# Motor_Control.net
KiCad netlist of a schematic drawn in Altium Designer
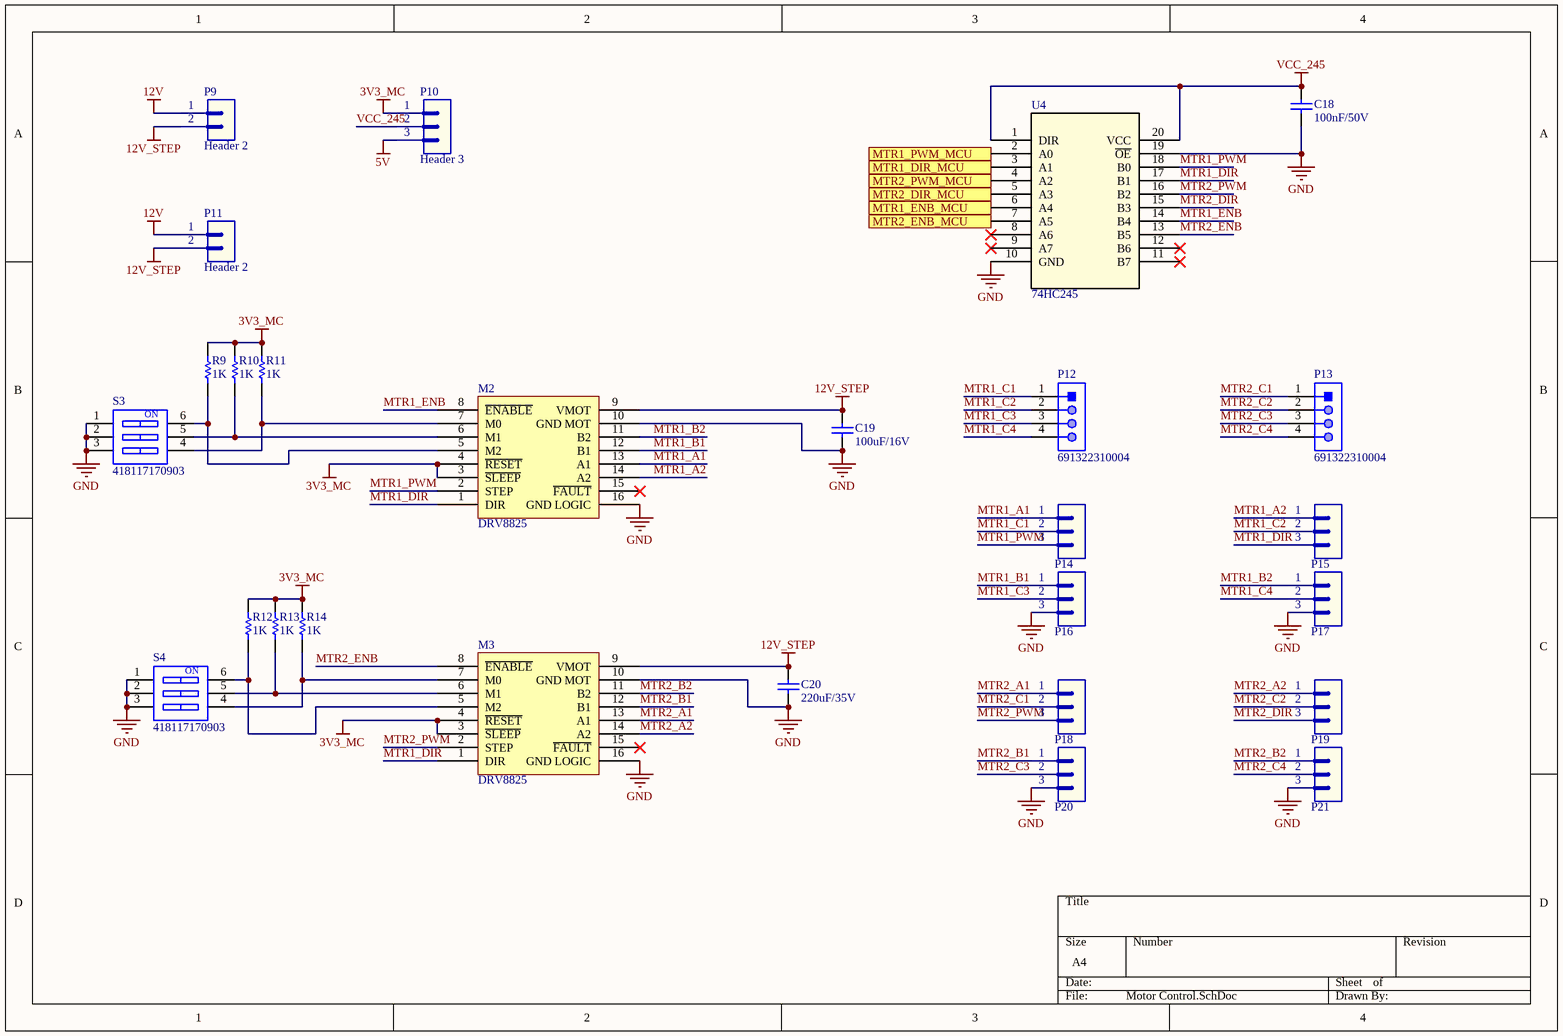
[diagram p0: Motor Control.SchDoc]

(export (version "E")
  (design (tool "Eeschema 10.0.6"))
  (components
    (comp (ref "C18")
      (value "100nF/50V")
      (footprint "CAP-SM-0805")
      (description "CAP CER 10UF 50V X5R 0805")
      (fields
        (field (name "MANUFACTURER") "Yageo")
        (field (name "MANUFACTURER PART NUMBER") "CC0805KKX5R9BB106")
      )
      (libsource (lib "Capacitor") (part "Cap-10uF-50V-0805"))
    )
    (comp (ref "C19")
      (value "100uF/16V")
      (footprint "CAP-SM-0805")
      (description "CAP CER 1000PF 100V X7R 0805")
      (fields
        (field (name "MANUFACTURER") "Johanson Dielectrics Inc.")
        (field (name "MANUFACTURER PART NUMBER") "101X15W102MV4E")
      )
      (libsource (lib "Capacitor") (part "Cap-1nF-50V-0805"))
    )
    (comp (ref "C20")
      (value "220uF/35V")
      (footprint "CAP-SM-0805")
      (description "CAP CER 1000PF 100V X7R 0805")
      (fields
        (field (name "MANUFACTURER") "Johanson Dielectrics Inc.")
        (field (name "MANUFACTURER PART NUMBER") "101X15W102MV4E")
      )
      (libsource (lib "Capacitor") (part "Cap-1nF-50V-0805"))
    )
    (comp (ref "M2") (value "DRV8825") (footprint "DRV8825") (libsource (lib "Schlib1") (part "DRV8825")))
    (comp (ref "M3") (value "DRV8825") (footprint "DRV8825") (libsource (lib "Schlib1") (part "DRV8825")))
    (comp (ref "P9")
      (value "Header 2")
      (footprint "JP2")
      (description "Header, 2-Pin")
      (fields (field (name "PUBLISHER") "Altium Limited"))
      (libsource (lib "PIF_C16_lib") (part "Header 2"))
    )
    (comp (ref "P10")
      (value "Header 3")
      (footprint "JP3")
      (description "Header, 3-Pin")
      (fields (field (name "PUBLISHER") "Altium Limited"))
      (libsource (lib "PIF_C16_lib") (part "Header 3"))
    )
    (comp (ref "P11")
      (value "Header 2")
      (footprint "JP2")
      (description "Header, 2-Pin")
      (fields (field (name "PUBLISHER") "Altium Limited"))
      (libsource (lib "PIF_C16_lib") (part "Header 2"))
    )
    (comp (ref "P12")
      (value "691322310004")
      (footprint "691322310004")
      (description "WR-TBL Serie 322 Horizontal PCB Header, Pluggable, pitch 3.81mm, 4p")
      (fields (field (name "PUBLISHER") "Wurth Elektronik"))
      (libsource (lib "691101710002_Altium_WR-TBL_rev19a") (part "691322310004"))
    )
    (comp (ref "P13")
      (value "691322310004")
      (footprint "691322310004")
      (description "WR-TBL Serie 322 Horizontal PCB Header, Pluggable, pitch 3.81mm, 4p")
      (fields (field (name "PUBLISHER") "Wurth Elektronik"))
      (libsource (lib "691101710002_Altium_WR-TBL_rev19a") (part "691322310004"))
    )
    (comp (ref "P14")
      (value "Header 3")
      (footprint "JP3")
      (description "Header, 3-Pin")
      (fields (field (name "PUBLISHER") "Altium Limited"))
      (libsource (lib "Header-connector") (part "Header 3"))
    )
    (comp (ref "P15")
      (value "Header 3")
      (footprint "JP3")
      (description "Header, 3-Pin")
      (fields (field (name "PUBLISHER") "Altium Limited"))
      (libsource (lib "Header-connector") (part "Header 3"))
    )
    (comp (ref "P16")
      (value "Header 3")
      (footprint "JP3")
      (description "Header, 3-Pin")
      (fields (field (name "PUBLISHER") "Altium Limited"))
      (libsource (lib "Header-connector") (part "Header 3"))
    )
    (comp (ref "P17")
      (value "Header 3")
      (footprint "JP3")
      (description "Header, 3-Pin")
      (fields (field (name "PUBLISHER") "Altium Limited"))
      (libsource (lib "Header-connector") (part "Header 3"))
    )
    (comp (ref "P18")
      (value "Header 3")
      (footprint "JP3")
      (description "Header, 3-Pin")
      (fields (field (name "PUBLISHER") "Altium Limited"))
      (libsource (lib "Header-connector") (part "Header 3"))
    )
    (comp (ref "P19")
      (value "Header 3")
      (footprint "JP3")
      (description "Header, 3-Pin")
      (fields (field (name "PUBLISHER") "Altium Limited"))
      (libsource (lib "Header-connector") (part "Header 3"))
    )
    (comp (ref "P20")
      (value "Header 3")
      (footprint "JP3")
      (description "Header, 3-Pin")
      (fields (field (name "PUBLISHER") "Altium Limited"))
      (libsource (lib "Header-connector") (part "Header 3"))
    )
    (comp (ref "P21")
      (value "Header 3")
      (footprint "JP3")
      (description "Header, 3-Pin")
      (fields (field (name "PUBLISHER") "Altium Limited"))
      (libsource (lib "Header-connector") (part "Header 3"))
    )
    (comp (ref "R9")
      (value "1K")
      (footprint "Resistor:RES-SM-0805")
      (description "RES 1K OHM 1% 1/4W 0805")
      (fields
        (field (name "MANUFACTURER") "Stackpole Electronics Inc")
        (field (name "MANUFACTURER PART NUMBER") "RNCP0805FTD1K00")
      )
      (libsource (lib "Resistor") (part "Res-1K-0805"))
    )
    (comp (ref "R10")
      (value "1K")
      (footprint "Resistor:RES-SM-0805")
      (description "RES 1K OHM 1% 1/4W 0805")
      (fields
        (field (name "MANUFACTURER") "Stackpole Electronics Inc")
        (field (name "MANUFACTURER PART NUMBER") "RNCP0805FTD1K00")
      )
      (libsource (lib "Resistor") (part "Res-1K-0805"))
    )
    (comp (ref "R11")
      (value "1K")
      (footprint "Resistor:RES-SM-0805")
      (description "RES 1K OHM 1% 1/4W 0805")
      (fields
        (field (name "MANUFACTURER") "Stackpole Electronics Inc")
        (field (name "MANUFACTURER PART NUMBER") "RNCP0805FTD1K00")
      )
      (libsource (lib "Resistor") (part "Res-1K-0805"))
    )
    (comp (ref "R12")
      (value "1K")
      (footprint "Resistor:RES-SM-0805")
      (description "RES 1K OHM 1% 1/4W 0805")
      (fields
        (field (name "MANUFACTURER") "Stackpole Electronics Inc")
        (field (name "MANUFACTURER PART NUMBER") "RNCP0805FTD1K00")
      )
      (libsource (lib "Resistor") (part "Res-1K-0805"))
    )
    (comp (ref "R13")
      (value "1K")
      (footprint "Resistor:RES-SM-0805")
      (description "RES 1K OHM 1% 1/4W 0805")
      (fields
        (field (name "MANUFACTURER") "Stackpole Electronics Inc")
        (field (name "MANUFACTURER PART NUMBER") "RNCP0805FTD1K00")
      )
      (libsource (lib "Resistor") (part "Res-1K-0805"))
    )
    (comp (ref "R14")
      (value "1K")
      (footprint "Resistor:RES-SM-0805")
      (description "RES 1K OHM 1% 1/4W 0805")
      (fields
        (field (name "MANUFACTURER") "Stackpole Electronics Inc")
        (field (name "MANUFACTURER PART NUMBER") "RNCP0805FTD1K00")
      )
      (libsource (lib "Resistor") (part "Res-1K-0805"))
    )
    (comp (ref "S3")
      (value "418117170903")
      (footprint "418117170903")
      (description "WS-DITV Compact THT Dip Switch, Flat Actuator, pitch 2.54mm, 3p")
      (fields (field (name "PUBLISHER") "Wurth Elektronik"))
      (libsource (lib "418117170903_Altium_WS-DITV_rev19a") (part "418117170903"))
    )
    (comp (ref "S4")
      (value "418117170903")
      (footprint "418117170903")
      (description "WS-DITV Compact THT Dip Switch, Flat Actuator, pitch 2.54mm, 3p")
      (fields (field (name "PUBLISHER") "Wurth Elektronik"))
      (libsource (lib "418117170903_Altium_WS-DITV_rev19a") (part "418117170903"))
    )
    (comp (ref "U4")
      (value "74HC245")
      (footprint "74HC245,625")
      (description "No Description Available")
      (fields (field (name "COPYRIGHT") "Copyright (C) 2018 Accelerated Designs. All rights reserved"))
      (libsource (lib "Integrated_Library") (part "74HC245"))
    )
  )
  (nets
    (net (code "1") (name "/MTR1_A1") (class "Default")
      (node (ref "M2") (pin "13") (pinfunction "A1_13") (pintype "passive"))
      (node (ref "P14") (pin "1") (pinfunction "1_1") (pintype "passive"))
    )
    (net (code "2") (name "/MTR1_A2") (class "Default")
      (node (ref "M2") (pin "14") (pinfunction "A2_14") (pintype "passive"))
      (node (ref "P15") (pin "1") (pinfunction "1_1") (pintype "passive"))
    )
    (net (code "3") (name "/MTR1_B1") (class "Default")
      (node (ref "M2") (pin "12") (pinfunction "B1_12") (pintype "passive"))
      (node (ref "P16") (pin "1") (pinfunction "1_1") (pintype "passive"))
    )
    (net (code "4") (name "/MTR1_B2") (class "Default")
      (node (ref "M2") (pin "11") (pinfunction "B2_11") (pintype "passive"))
      (node (ref "P17") (pin "1") (pinfunction "1_1") (pintype "passive"))
    )
    (net (code "5") (name "/MTR1_C1") (class "Default")
      (node (ref "P12") (pin "1") (pinfunction "1_1") (pintype "passive"))
      (node (ref "P14") (pin "2") (pinfunction "2_2") (pintype "passive"))
    )
    (net (code "6") (name "/MTR1_C2") (class "Default")
      (node (ref "P12") (pin "2") (pinfunction "2_2") (pintype "passive"))
      (node (ref "P15") (pin "2") (pinfunction "2_2") (pintype "passive"))
    )
    (net (code "7") (name "/MTR1_C3") (class "Default")
      (node (ref "P12") (pin "3") (pinfunction "3_3") (pintype "passive"))
      (node (ref "P16") (pin "2") (pinfunction "2_2") (pintype "passive"))
    )
    (net (code "8") (name "/MTR1_C4") (class "Default")
      (node (ref "P12") (pin "4") (pinfunction "4_4") (pintype "passive"))
      (node (ref "P17") (pin "2") (pinfunction "2_2") (pintype "passive"))
    )
    (net (code "9") (name "/MTR1_DIR") (class "Default")
      (node (ref "M2") (pin "1") (pinfunction "DIR_1") (pintype "passive"))
      (node (ref "M3") (pin "1") (pinfunction "DIR_1") (pintype "passive"))
      (node (ref "P15") (pin "3") (pinfunction "3_3") (pintype "passive"))
      (node (ref "U4") (pin "17") (pinfunction "B1_17") (pintype "passive"))
    )
    (net (code "10") (name "/MTR1_DIR_MCU") (class "Default")
      (node (ref "U4") (pin "3") (pinfunction "A1_3") (pintype "passive"))
    )
    (net (code "11") (name "/MTR1_ENB") (class "Default")
      (node (ref "M2") (pin "8") (pinfunction "~{ENABLE}_8") (pintype "passive"))
      (node (ref "U4") (pin "14") (pinfunction "B4_14") (pintype "passive"))
    )
    (net (code "12") (name "/MTR1_ENB_MCU") (class "Default")
      (node (ref "U4") (pin "6") (pinfunction "A4_6") (pintype "passive"))
    )
    (net (code "13") (name "/MTR1_PWM") (class "Default")
      (node (ref "M2") (pin "2") (pinfunction "STEP_2") (pintype "passive"))
      (node (ref "P14") (pin "3") (pinfunction "3_3") (pintype "passive"))
      (node (ref "U4") (pin "18") (pinfunction "B0_18") (pintype "passive"))
    )
    (net (code "14") (name "/MTR1_PWM_MCU") (class "Default")
      (node (ref "U4") (pin "2") (pinfunction "A0_2") (pintype "passive"))
    )
    (net (code "15") (name "/MTR2_A1") (class "Default")
      (node (ref "M3") (pin "13") (pinfunction "A1_13") (pintype "passive"))
      (node (ref "P18") (pin "1") (pinfunction "1_1") (pintype "passive"))
    )
    (net (code "16") (name "/MTR2_A2") (class "Default")
      (node (ref "M3") (pin "14") (pinfunction "A2_14") (pintype "passive"))
      (node (ref "P19") (pin "1") (pinfunction "1_1") (pintype "passive"))
    )
    (net (code "17") (name "/MTR2_B1") (class "Default")
      (node (ref "M3") (pin "12") (pinfunction "B1_12") (pintype "passive"))
      (node (ref "P20") (pin "1") (pinfunction "1_1") (pintype "passive"))
    )
    (net (code "18") (name "/MTR2_B2") (class "Default")
      (node (ref "M3") (pin "11") (pinfunction "B2_11") (pintype "passive"))
      (node (ref "P21") (pin "1") (pinfunction "1_1") (pintype "passive"))
    )
    (net (code "19") (name "/MTR2_C1") (class "Default")
      (node (ref "P13") (pin "1") (pinfunction "1_1") (pintype "passive"))
      (node (ref "P18") (pin "2") (pinfunction "2_2") (pintype "passive"))
    )
    (net (code "20") (name "/MTR2_C2") (class "Default")
      (node (ref "P13") (pin "2") (pinfunction "2_2") (pintype "passive"))
      (node (ref "P19") (pin "2") (pinfunction "2_2") (pintype "passive"))
    )
    (net (code "21") (name "/MTR2_C3") (class "Default")
      (node (ref "P13") (pin "3") (pinfunction "3_3") (pintype "passive"))
      (node (ref "P20") (pin "2") (pinfunction "2_2") (pintype "passive"))
    )
    (net (code "22") (name "/MTR2_C4") (class "Default")
      (node (ref "P13") (pin "4") (pinfunction "4_4") (pintype "passive"))
      (node (ref "P21") (pin "2") (pinfunction "2_2") (pintype "passive"))
    )
    (net (code "23") (name "/MTR2_DIR") (class "Default")
      (node (ref "P19") (pin "3") (pinfunction "3_3") (pintype "passive"))
      (node (ref "U4") (pin "15") (pinfunction "B3_15") (pintype "passive"))
    )
    (net (code "24") (name "/MTR2_DIR_MCU") (class "Default")
      (node (ref "U4") (pin "5") (pinfunction "A3_5") (pintype "passive"))
    )
    (net (code "25") (name "/MTR2_ENB") (class "Default")
      (node (ref "M3") (pin "8") (pinfunction "~{ENABLE}_8") (pintype "passive"))
      (node (ref "U4") (pin "13") (pinfunction "B5_13") (pintype "passive"))
    )
    (net (code "26") (name "/MTR2_ENB_MCU") (class "Default")
      (node (ref "U4") (pin "7") (pinfunction "A5_7") (pintype "passive"))
    )
    (net (code "27") (name "/MTR2_PWM") (class "Default")
      (node (ref "M3") (pin "2") (pinfunction "STEP_2") (pintype "passive"))
      (node (ref "P18") (pin "3") (pinfunction "3_3") (pintype "passive"))
      (node (ref "U4") (pin "16") (pinfunction "B2_16") (pintype "passive"))
    )
    (net (code "28") (name "/MTR2_PWM_MCU") (class "Default")
      (node (ref "U4") (pin "4") (pinfunction "A2_4") (pintype "passive"))
    )
    (net (code "29") (name "3V3_MC") (class "Default")
      (node (ref "M2") (pin "3") (pinfunction "~{SLEEP}_3") (pintype "passive"))
      (node (ref "M2") (pin "4") (pinfunction "~{RESET}_4") (pintype "passive"))
      (node (ref "M3") (pin "3") (pinfunction "~{SLEEP}_3") (pintype "passive"))
      (node (ref "M3") (pin "4") (pinfunction "~{RESET}_4") (pintype "passive"))
      (node (ref "P10") (pin "1") (pinfunction "1_1") (pintype "passive"))
      (node (ref "R10") (pin "2") (pinfunction "2_2") (pintype "passive"))
      (node (ref "R11") (pin "2") (pinfunction "2_2") (pintype "passive"))
      (node (ref "R12") (pin "2") (pinfunction "2_2") (pintype "passive"))
      (node (ref "R13") (pin "2") (pinfunction "2_2") (pintype "passive"))
      (node (ref "R14") (pin "2") (pinfunction "2_2") (pintype "passive"))
      (node (ref "R9") (pin "2") (pinfunction "2_2") (pintype "passive"))
    )
    (net (code "30") (name "5V") (class "Default")
      (node (ref "P10") (pin "3") (pinfunction "3_3") (pintype "passive"))
    )
    (net (code "31") (name "12V") (class "Default")
      (node (ref "P11") (pin "1") (pinfunction "1_1") (pintype "passive"))
      (node (ref "P9") (pin "1") (pinfunction "1_1") (pintype "passive"))
    )
    (net (code "32") (name "12V_STEP") (class "Default")
      (node (ref "C19") (pin "2") (pinfunction "2_2") (pintype "passive"))
      (node (ref "C20") (pin "2") (pinfunction "2_2") (pintype "passive"))
      (node (ref "M2") (pin "9") (pinfunction "VMOT_9") (pintype "passive"))
      (node (ref "M3") (pin "9") (pinfunction "VMOT_9") (pintype "passive"))
      (node (ref "P11") (pin "2") (pinfunction "2_2") (pintype "passive"))
      (node (ref "P9") (pin "2") (pinfunction "2_2") (pintype "passive"))
    )
    (net (code "33") (name "GND") (class "Default")
      (node (ref "C18") (pin "1") (pinfunction "1_1") (pintype "passive"))
      (node (ref "C19") (pin "1") (pinfunction "1_1") (pintype "passive"))
      (node (ref "C20") (pin "1") (pinfunction "1_1") (pintype "passive"))
      (node (ref "M2") (pin "10") (pinfunction "GND_MOT_10") (pintype "passive"))
      (node (ref "M2") (pin "16") (pinfunction "GND_LOGIC_16") (pintype "passive"))
      (node (ref "M3") (pin "10") (pinfunction "GND_MOT_10") (pintype "passive"))
      (node (ref "M3") (pin "16") (pinfunction "GND_LOGIC_16") (pintype "passive"))
      (node (ref "P16") (pin "3") (pinfunction "3_3") (pintype "passive"))
      (node (ref "P17") (pin "3") (pinfunction "3_3") (pintype "passive"))
      (node (ref "P20") (pin "3") (pinfunction "3_3") (pintype "passive"))
      (node (ref "P21") (pin "3") (pinfunction "3_3") (pintype "passive"))
      (node (ref "S3") (pin "1") (pinfunction "1_1") (pintype "passive"))
      (node (ref "S3") (pin "2") (pinfunction "2_2") (pintype "passive"))
      (node (ref "S3") (pin "3") (pinfunction "3_3") (pintype "passive"))
      (node (ref "S4") (pin "1") (pinfunction "1_1") (pintype "passive"))
      (node (ref "S4") (pin "2") (pinfunction "2_2") (pintype "passive"))
      (node (ref "S4") (pin "3") (pinfunction "3_3") (pintype "passive"))
      (node (ref "U4") (pin "10") (pinfunction "GND_10") (pintype "passive"))
      (node (ref "U4") (pin "19") (pinfunction "~{OE}_19") (pintype "passive"))
    )
    (net (code "34") (name "Net-(M2-M0)") (class "Default")
      (node (ref "M2") (pin "7") (pinfunction "M0_7") (pintype "passive"))
      (node (ref "R11") (pin "1") (pinfunction "1_1") (pintype "passive"))
      (node (ref "S3") (pin "4") (pinfunction "4_4") (pintype "passive"))
    )
    (net (code "35") (name "Net-(M2-M1)") (class "Default")
      (node (ref "M2") (pin "6") (pinfunction "M1_6") (pintype "passive"))
      (node (ref "R10") (pin "1") (pinfunction "1_1") (pintype "passive"))
      (node (ref "S3") (pin "5") (pinfunction "5_5") (pintype "passive"))
    )
    (net (code "36") (name "Net-(M2-M2)") (class "Default")
      (node (ref "M2") (pin "5") (pinfunction "M2_5") (pintype "passive"))
      (node (ref "R9") (pin "1") (pinfunction "1_1") (pintype "passive"))
      (node (ref "S3") (pin "6") (pinfunction "6_6") (pintype "passive"))
    )
    (net (code "37") (name "Net-(M3-M0)") (class "Default")
      (node (ref "M3") (pin "7") (pinfunction "M0_7") (pintype "passive"))
      (node (ref "R14") (pin "1") (pinfunction "1_1") (pintype "passive"))
      (node (ref "S4") (pin "4") (pinfunction "4_4") (pintype "passive"))
    )
    (net (code "38") (name "Net-(M3-M1)") (class "Default")
      (node (ref "M3") (pin "6") (pinfunction "M1_6") (pintype "passive"))
      (node (ref "R13") (pin "1") (pinfunction "1_1") (pintype "passive"))
      (node (ref "S4") (pin "5") (pinfunction "5_5") (pintype "passive"))
    )
    (net (code "39") (name "Net-(M3-M2)") (class "Default")
      (node (ref "M3") (pin "5") (pinfunction "M2_5") (pintype "passive"))
      (node (ref "R12") (pin "1") (pinfunction "1_1") (pintype "passive"))
      (node (ref "S4") (pin "6") (pinfunction "6_6") (pintype "passive"))
    )
    (net (code "40") (name "VCC_245") (class "Default")
      (node (ref "C18") (pin "2") (pinfunction "2_2") (pintype "passive"))
      (node (ref "P10") (pin "2") (pinfunction "2_2") (pintype "passive"))
      (node (ref "U4") (pin "1") (pinfunction "DIR_1") (pintype "passive"))
      (node (ref "U4") (pin "20") (pinfunction "VCC_20") (pintype "passive"))
    )
    (net (code "41") (name "unconnected-(M2-~{FAULT}-Pad15)") (class "Default")
      (node (ref "M2") (pin "15") (pinfunction "~{FAULT}_15") (pintype "passive+no_connect"))
    )
    (net (code "42") (name "unconnected-(M3-~{FAULT}-Pad15)") (class "Default")
      (node (ref "M3") (pin "15") (pinfunction "~{FAULT}_15") (pintype "passive+no_connect"))
    )
    (net (code "43") (name "unconnected-(U4-A6-Pad8)") (class "Default")
      (node (ref "U4") (pin "8") (pinfunction "A6_8") (pintype "passive+no_connect"))
    )
    (net (code "44") (name "unconnected-(U4-A7-Pad9)") (class "Default")
      (node (ref "U4") (pin "9") (pinfunction "A7_9") (pintype "passive+no_connect"))
    )
    (net (code "45") (name "unconnected-(U4-B6-Pad12)") (class "Default")
      (node (ref "U4") (pin "12") (pinfunction "B6_12") (pintype "passive+no_connect"))
    )
    (net (code "46") (name "unconnected-(U4-B7-Pad11)") (class "Default")
      (node (ref "U4") (pin "11") (pinfunction "B7_11") (pintype "passive+no_connect"))
    )
  )
)
